# leaf_gen2_adapter.net
KiCad netlist of a schematic drawn in EAGLE
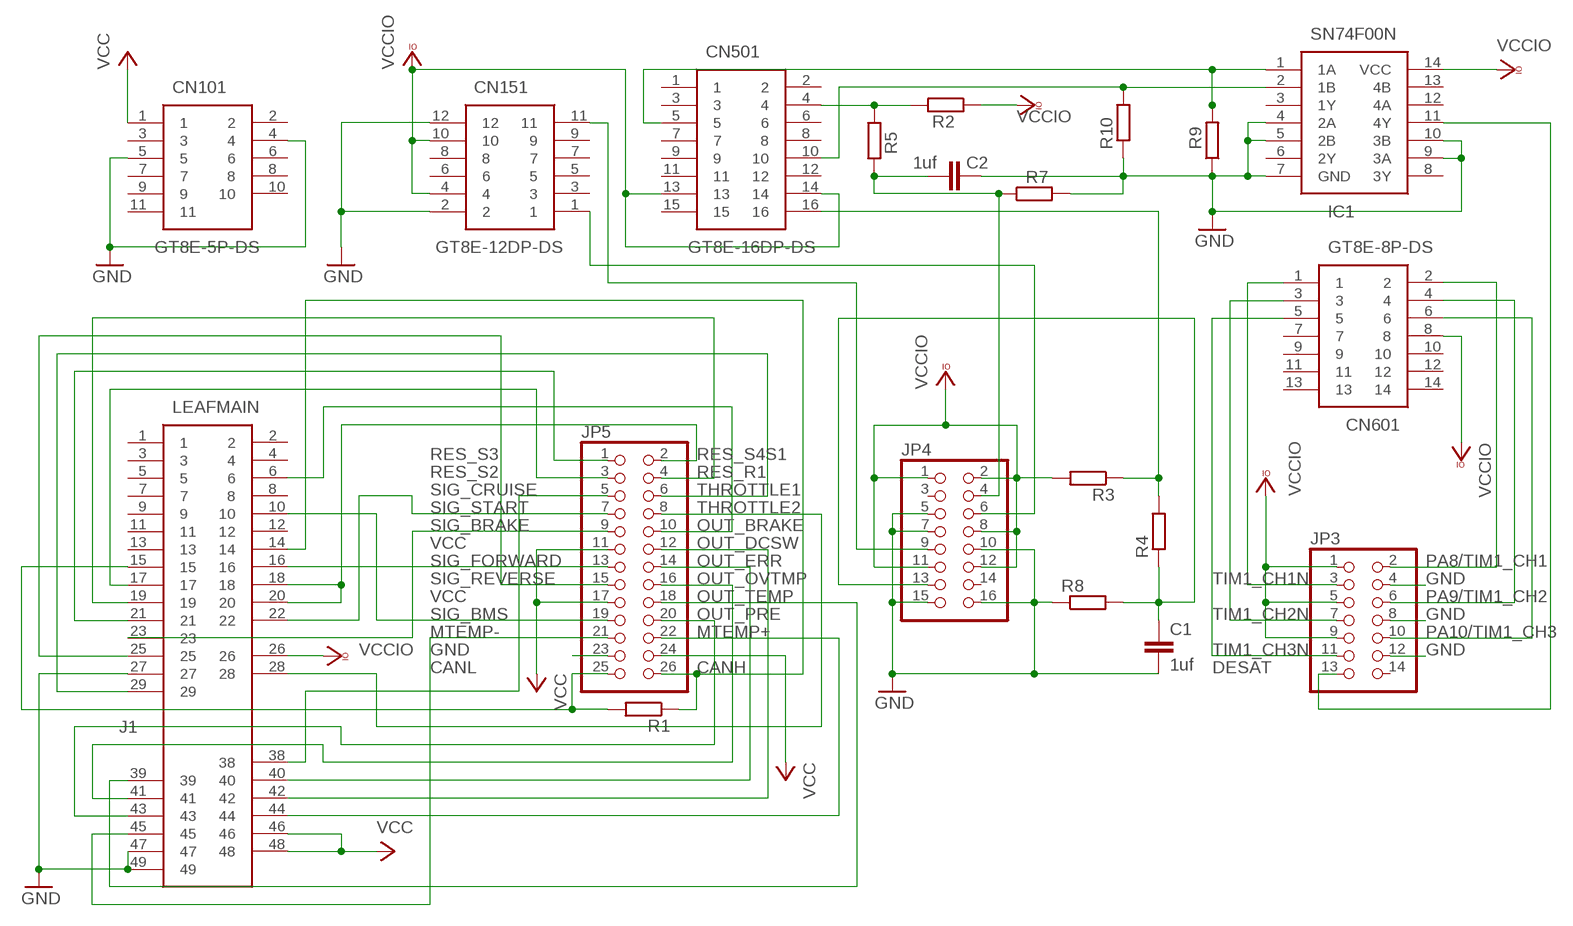
[diagram p0: schematic, sheet 1]

(export (version "E")
  (design (tool "Eeschema 10.0.6"))
  (components
    (comp (ref "C1")
      (value "1uf")
      (footprint "eagle-import:C025-024X044")
      (libsource (lib "eagle-import") (part "C-EU025-024X044"))
    )
    (comp (ref "C2")
      (value "1uf")
      (footprint "eagle-import:C025-024X044")
      (libsource (lib "eagle-import") (part "C-EU025-024X044"))
    )
    (comp (ref "CN101")
      (value "GT8E-5P-DS")
      (footprint "eagle-import:GT8E5PDS")
      (libsource (lib "eagle-import") (part "GT8E-5P-DS"))
    )
    (comp (ref "CN151")
      (value "GT8E-12DP-DS")
      (footprint "eagle-import:GT8E-12DP-DS")
      (libsource (lib "eagle-import") (part "GT8E-12DP-DS"))
    )
    (comp (ref "CN501")
      (value "GT8E-16DP-DS")
      (footprint "eagle-import:GT8E-16DP-DS")
      (libsource (lib "eagle-import") (part "GT8E-16DP-DS"))
    )
    (comp (ref "CN601")
      (value "GT8E-8P-DS")
      (footprint "eagle-import:GT8E8PDS")
      (libsource (lib "eagle-import") (part "GT8E-8P-DS"))
    )
    (comp (ref "IC1")
      (value "SN74F00N")
      (footprint "eagle-import:DIP254P762X508-14")
      (libsource (lib "eagle-import") (part "SN74F00N"))
    )
    (comp (ref "J1")
      (value "LEAFMAIN")
      (footprint "eagle-import:LEAFMAIN")
      (libsource (lib "eagle-import") (part "LEAFMAIN"))
    )
    (comp (ref "JP3")
      (value "PINHD-2X7")
      (footprint "eagle-import:2X07")
      (libsource (lib "eagle-import") (part "PINHD-2X7"))
    )
    (comp (ref "JP4")
      (value "PINHD-2X8")
      (footprint "eagle-import:2X08")
      (libsource (lib "eagle-import") (part "PINHD-2X8"))
    )
    (comp (ref "JP5")
      (value "PINHD-2X13")
      (footprint "eagle-import:2X13")
      (libsource (lib "eagle-import") (part "PINHD-2X13"))
    )
    (comp (ref "R1")
      (value "R-EU_0207/12")
      (footprint "eagle-import:0207_12")
      (libsource (lib "eagle-import") (part "R-EU_0207/12"))
    )
    (comp (ref "R2")
      (value "R-EU_0207/12")
      (footprint "eagle-import:0207_12")
      (libsource (lib "eagle-import") (part "R-EU_0207/12"))
    )
    (comp (ref "R3")
      (value "R-EU_0207/12")
      (footprint "eagle-import:0207_12")
      (libsource (lib "eagle-import") (part "R-EU_0207/12"))
    )
    (comp (ref "R4")
      (value "R-EU_0207/12")
      (footprint "eagle-import:0207_12")
      (libsource (lib "eagle-import") (part "R-EU_0207/12"))
    )
    (comp (ref "R5")
      (value "R-EU_0207/12")
      (footprint "eagle-import:0207_12")
      (libsource (lib "eagle-import") (part "R-EU_0207/12"))
    )
    (comp (ref "R7")
      (value "R-EU_0207/12")
      (footprint "eagle-import:0207_12")
      (libsource (lib "eagle-import") (part "R-EU_0207/12"))
    )
    (comp (ref "R8")
      (value "R-EU_0207/12")
      (footprint "eagle-import:0207_12")
      (libsource (lib "eagle-import") (part "R-EU_0207/12"))
    )
    (comp (ref "R9")
      (value "R-EU_0207/12")
      (footprint "eagle-import:0207_12")
      (libsource (lib "eagle-import") (part "R-EU_0207/12"))
    )
    (comp (ref "R10")
      (value "R-EU_0207/12")
      (footprint "eagle-import:0207_12")
      (libsource (lib "eagle-import") (part "R-EU_0207/12"))
    )
  )
  (nets
    (net (code "1") (name "/CANH") (class "Default")
      (node (ref "J1") (pin "14") (pinfunction "14_14") (pintype "bidirectional"))
      (node (ref "JP5") (pin "26") (pinfunction "26_26") (pintype "passive"))
      (node (ref "R1") (pin "1") (pinfunction "1_1") (pintype "passive"))
    )
    (net (code "2") (name "/CANL") (class "Default")
      (node (ref "J1") (pin "15") (pinfunction "15_15") (pintype "bidirectional"))
      (node (ref "JP5") (pin "25") (pinfunction "25_25") (pintype "passive"))
      (node (ref "R1") (pin "2") (pinfunction "2_2") (pintype "passive"))
    )
    (net (code "3") (name "/DESAT") (class "Default")
      (node (ref "IC1") (pin "11") (pinfunction "4Y_11") (pintype "bidirectional"))
      (node (ref "JP3") (pin "13") (pinfunction "13_13") (pintype "passive"))
    )
    (net (code "4") (name "/MTEMP+") (class "Default")
      (node (ref "J1") (pin "44") (pinfunction "44_44") (pintype "bidirectional"))
      (node (ref "JP5") (pin "22") (pinfunction "22_22") (pintype "passive"))
    )
    (net (code "5") (name "/MTEMP-") (class "Default")
      (node (ref "J1") (pin "45") (pinfunction "45_45") (pintype "bidirectional"))
      (node (ref "JP5") (pin "21") (pinfunction "21_21") (pintype "passive"))
    )
    (net (code "6") (name "/OUT_BRAKE") (class "Default")
      (node (ref "J1") (pin "6") (pinfunction "6_6") (pintype "bidirectional"))
      (node (ref "JP5") (pin "10") (pinfunction "10_10") (pintype "passive"))
    )
    (net (code "7") (name "/OUT_DCSW") (class "Default")
      (node (ref "J1") (pin "42") (pinfunction "42_42") (pintype "bidirectional"))
      (node (ref "JP5") (pin "12") (pinfunction "12_12") (pintype "passive"))
    )
    (net (code "8") (name "/OUT_ERR") (class "Default")
      (node (ref "J1") (pin "40") (pinfunction "40_40") (pintype "bidirectional"))
      (node (ref "JP5") (pin "14") (pinfunction "14_14") (pintype "passive"))
    )
    (net (code "9") (name "/OUT_OVTMP") (class "Default")
      (node (ref "J1") (pin "41") (pinfunction "41_41") (pintype "bidirectional"))
      (node (ref "JP5") (pin "16") (pinfunction "16_16") (pintype "passive"))
    )
    (net (code "10") (name "/OUT_PRE") (class "Default")
      (node (ref "J1") (pin "43") (pinfunction "43_43") (pintype "bidirectional"))
      (node (ref "JP5") (pin "20") (pinfunction "20_20") (pintype "passive"))
    )
    (net (code "11") (name "/OUT_TEMP") (class "Default")
      (node (ref "J1") (pin "39") (pinfunction "39_39") (pintype "bidirectional"))
      (node (ref "JP5") (pin "18") (pinfunction "18_18") (pintype "passive"))
    )
    (net (code "12") (name "/PA8{slash}TIM1_CH1") (class "Default")
      (node (ref "CN601") (pin "2") (pinfunction "2_2") (pintype "bidirectional"))
      (node (ref "JP3") (pin "2") (pinfunction "2_2") (pintype "passive"))
    )
    (net (code "13") (name "/PA9{slash}TIM1_CH2") (class "Default")
      (node (ref "CN601") (pin "4") (pinfunction "4_4") (pintype "bidirectional"))
      (node (ref "JP3") (pin "6") (pinfunction "6_6") (pintype "passive"))
    )
    (net (code "14") (name "/PA10{slash}TIM1_CH3") (class "Default")
      (node (ref "CN601") (pin "6") (pinfunction "6_6") (pintype "bidirectional"))
      (node (ref "JP3") (pin "10") (pinfunction "10_10") (pintype "passive"))
    )
    (net (code "15") (name "/RES_R1") (class "Default")
      (node (ref "J1") (pin "19") (pinfunction "19_19") (pintype "bidirectional"))
      (node (ref "JP5") (pin "4") (pinfunction "4_4") (pintype "passive"))
    )
    (net (code "16") (name "/RES_S2") (class "Default")
      (node (ref "J1") (pin "17") (pinfunction "17_17") (pintype "bidirectional"))
      (node (ref "JP5") (pin "3") (pinfunction "3_3") (pintype "passive"))
    )
    (net (code "17") (name "/RES_S3") (class "Default")
      (node (ref "J1") (pin "21") (pinfunction "21_21") (pintype "bidirectional"))
      (node (ref "JP5") (pin "1") (pinfunction "1_1") (pintype "passive"))
    )
    (net (code "18") (name "/RES_S4S1") (class "Default")
      (node (ref "J1") (pin "18") (pinfunction "18_18") (pintype "bidirectional"))
      (node (ref "J1") (pin "20") (pinfunction "20_20") (pintype "bidirectional"))
      (node (ref "JP5") (pin "2") (pinfunction "2_2") (pintype "passive"))
    )
    (net (code "19") (name "/SIG_BMS") (class "Default")
      (node (ref "J1") (pin "10") (pinfunction "10_10") (pintype "bidirectional"))
      (node (ref "JP5") (pin "19") (pinfunction "19_19") (pintype "passive"))
    )
    (net (code "20") (name "/SIG_BRAKE") (class "Default")
      (node (ref "J1") (pin "23") (pinfunction "23_23") (pintype "bidirectional"))
      (node (ref "JP5") (pin "9") (pinfunction "9_9") (pintype "passive"))
    )
    (net (code "21") (name "/SIG_CRUISE") (class "Default")
      (node (ref "J1") (pin "38") (pinfunction "38_38") (pintype "bidirectional"))
      (node (ref "JP5") (pin "5") (pinfunction "5_5") (pintype "passive"))
    )
    (net (code "22") (name "/SIG_FORWARD") (class "Default")
      (node (ref "J1") (pin "16") (pinfunction "16_16") (pintype "bidirectional"))
      (node (ref "JP5") (pin "13") (pinfunction "13_13") (pintype "passive"))
    )
    (net (code "23") (name "/SIG_REVERSE") (class "Default")
      (node (ref "J1") (pin "25") (pinfunction "25_25") (pintype "bidirectional"))
      (node (ref "JP5") (pin "15") (pinfunction "15_15") (pintype "passive"))
    )
    (net (code "24") (name "/SIG_START") (class "Default")
      (node (ref "J1") (pin "22") (pinfunction "22_22") (pintype "bidirectional"))
      (node (ref "JP5") (pin "7") (pinfunction "7_7") (pintype "passive"))
    )
    (net (code "25") (name "/THROTTLE1") (class "Default")
      (node (ref "J1") (pin "29") (pinfunction "29_29") (pintype "bidirectional"))
      (node (ref "JP5") (pin "6") (pinfunction "6_6") (pintype "passive"))
    )
    (net (code "26") (name "/THROTTLE2") (class "Default")
      (node (ref "J1") (pin "28") (pinfunction "28_28") (pintype "bidirectional"))
      (node (ref "JP5") (pin "8") (pinfunction "8_8") (pintype "passive"))
    )
    (net (code "27") (name "/TIM1_CH1N") (class "Default")
      (node (ref "CN601") (pin "1") (pinfunction "1_1") (pintype "bidirectional"))
      (node (ref "JP3") (pin "3") (pinfunction "3_3") (pintype "passive"))
    )
    (net (code "28") (name "/TIM1_CH2N") (class "Default")
      (node (ref "CN601") (pin "3") (pinfunction "3_3") (pintype "bidirectional"))
      (node (ref "JP3") (pin "7") (pinfunction "7_7") (pintype "passive"))
    )
    (net (code "29") (name "/TIM1_CH3N") (class "Default")
      (node (ref "CN601") (pin "5") (pinfunction "5_5") (pintype "bidirectional"))
      (node (ref "JP3") (pin "11") (pinfunction "11_11") (pintype "passive"))
    )
    (net (code "30") (name "GND") (class "Default")
      (node (ref "C1") (pin "2") (pinfunction "2_2") (pintype "passive"))
      (node (ref "C2") (pin "1") (pinfunction "1_1") (pintype "passive"))
      (node (ref "CN101") (pin "4") (pinfunction "4_4") (pintype "bidirectional"))
      (node (ref "CN101") (pin "5") (pinfunction "5_5") (pintype "bidirectional"))
      (node (ref "CN151") (pin "12") (pinfunction "12_12") (pintype "bidirectional"))
      (node (ref "CN151") (pin "2") (pinfunction "2_2") (pintype "bidirectional"))
      (node (ref "IC1") (pin "10") (pinfunction "3B_10") (pintype "bidirectional"))
      (node (ref "IC1") (pin "4") (pinfunction "2A_4") (pintype "bidirectional"))
      (node (ref "IC1") (pin "5") (pinfunction "2B_5") (pintype "bidirectional"))
      (node (ref "IC1") (pin "7") (pinfunction "GND_7") (pintype "bidirectional"))
      (node (ref "IC1") (pin "9") (pinfunction "3A_9") (pintype "bidirectional"))
      (node (ref "J1") (pin "27") (pinfunction "27_27") (pintype "bidirectional"))
      (node (ref "J1") (pin "47") (pinfunction "47_47") (pintype "bidirectional"))
      (node (ref "J1") (pin "49") (pinfunction "49_49") (pintype "bidirectional"))
      (node (ref "JP3") (pin "12") (pinfunction "12_12") (pintype "passive"))
      (node (ref "JP3") (pin "4") (pinfunction "4_4") (pintype "passive"))
      (node (ref "JP3") (pin "8") (pinfunction "8_8") (pintype "passive"))
      (node (ref "JP4") (pin "10") (pinfunction "10_10") (pintype "passive"))
      (node (ref "JP4") (pin "15") (pinfunction "15_15") (pintype "passive"))
      (node (ref "JP4") (pin "16") (pinfunction "16_16") (pintype "passive"))
      (node (ref "JP4") (pin "5") (pinfunction "5_5") (pintype "passive"))
      (node (ref "JP4") (pin "7") (pinfunction "7_7") (pintype "passive"))
      (node (ref "JP5") (pin "23") (pinfunction "23_23") (pintype "passive"))
      (node (ref "R10") (pin "1") (pinfunction "1_1") (pintype "passive"))
      (node (ref "R7") (pin "2") (pinfunction "2_2") (pintype "passive"))
      (node (ref "R8") (pin "1") (pinfunction "1_1") (pintype "passive"))
      (node (ref "R9") (pin "1") (pinfunction "1_1") (pintype "passive"))
    )
    (net (code "31") (name "Net-(C1-Pad1)") (class "Default")
      (node (ref "C1") (pin "1") (pinfunction "1_1") (pintype "passive"))
      (node (ref "JP4") (pin "13") (pinfunction "13_13") (pintype "passive"))
      (node (ref "R4") (pin "1") (pinfunction "1_1") (pintype "passive"))
      (node (ref "R8") (pin "2") (pinfunction "2_2") (pintype "passive"))
    )
    (net (code "32") (name "Net-(C2-Pad2)") (class "Default")
      (node (ref "C2") (pin "2") (pinfunction "2_2") (pintype "passive"))
      (node (ref "JP4") (pin "4") (pinfunction "4_4") (pintype "passive"))
      (node (ref "R5") (pin "2") (pinfunction "2_2") (pintype "passive"))
      (node (ref "R7") (pin "1") (pinfunction "1_1") (pintype "passive"))
    )
    (net (code "33") (name "Net-(CN151-Pad1)") (class "Default")
      (node (ref "CN151") (pin "1") (pinfunction "1_1") (pintype "bidirectional"))
      (node (ref "JP4") (pin "6") (pinfunction "6_6") (pintype "passive"))
    )
    (net (code "34") (name "Net-(CN151-Pad11)") (class "Default")
      (node (ref "CN151") (pin "11") (pinfunction "11_11") (pintype "bidirectional"))
      (node (ref "JP4") (pin "9") (pinfunction "9_9") (pintype "passive"))
    )
    (net (code "35") (name "Net-(CN501-Pad4)") (class "Default")
      (node (ref "CN501") (pin "4") (pinfunction "4_4") (pintype "bidirectional"))
      (node (ref "R2") (pin "2") (pinfunction "2_2") (pintype "passive"))
      (node (ref "R5") (pin "1") (pinfunction "1_1") (pintype "passive"))
    )
    (net (code "36") (name "Net-(CN501-Pad16)") (class "Default")
      (node (ref "CN501") (pin "16") (pinfunction "16_16") (pintype "bidirectional"))
      (node (ref "R3") (pin "1") (pinfunction "1_1") (pintype "passive"))
      (node (ref "R4") (pin "2") (pinfunction "2_2") (pintype "passive"))
    )
    (net (code "37") (name "Net-(IC1-1A)") (class "Default")
      (node (ref "CN501") (pin "5") (pinfunction "5_5") (pintype "bidirectional"))
      (node (ref "IC1") (pin "1") (pinfunction "1A_1") (pintype "bidirectional"))
      (node (ref "R9") (pin "2") (pinfunction "2_2") (pintype "passive"))
    )
    (net (code "38") (name "Net-(IC1-1B)") (class "Default")
      (node (ref "CN501") (pin "10") (pinfunction "10_10") (pintype "bidirectional"))
      (node (ref "IC1") (pin "2") (pinfunction "1B_2") (pintype "bidirectional"))
      (node (ref "R10") (pin "2") (pinfunction "2_2") (pintype "passive"))
    )
    (net (code "39") (name "VCC") (class "Default")
      (node (ref "CN101") (pin "1") (pinfunction "1_1") (pintype "bidirectional"))
      (node (ref "J1") (pin "46") (pinfunction "46_46") (pintype "bidirectional"))
      (node (ref "J1") (pin "48") (pinfunction "48_48") (pintype "bidirectional"))
      (node (ref "JP5") (pin "11") (pinfunction "11_11") (pintype "passive"))
      (node (ref "JP5") (pin "17") (pinfunction "17_17") (pintype "passive"))
      (node (ref "JP5") (pin "24") (pinfunction "24_24") (pintype "passive"))
    )
    (net (code "40") (name "VCCIO") (class "Default")
      (node (ref "CN151") (pin "10") (pinfunction "10_10") (pintype "bidirectional"))
      (node (ref "CN151") (pin "4") (pinfunction "4_4") (pintype "bidirectional"))
      (node (ref "CN501") (pin "13") (pinfunction "13_13") (pintype "bidirectional"))
      (node (ref "CN501") (pin "14") (pinfunction "14_14") (pintype "bidirectional"))
      (node (ref "CN601") (pin "8") (pinfunction "8_8") (pintype "bidirectional"))
      (node (ref "IC1") (pin "14") (pinfunction "VCC_14") (pintype "bidirectional"))
      (node (ref "J1") (pin "26") (pinfunction "26_26") (pintype "bidirectional"))
      (node (ref "JP3") (pin "1") (pinfunction "1_1") (pintype "passive"))
      (node (ref "JP3") (pin "5") (pinfunction "5_5") (pintype "passive"))
      (node (ref "JP3") (pin "9") (pinfunction "9_9") (pintype "passive"))
      (node (ref "JP4") (pin "1") (pinfunction "1_1") (pintype "passive"))
      (node (ref "JP4") (pin "11") (pinfunction "11_11") (pintype "passive"))
      (node (ref "JP4") (pin "12") (pinfunction "12_12") (pintype "passive"))
      (node (ref "JP4") (pin "2") (pinfunction "2_2") (pintype "passive"))
      (node (ref "JP4") (pin "8") (pinfunction "8_8") (pintype "passive"))
      (node (ref "R2") (pin "1") (pinfunction "1_1") (pintype "passive"))
      (node (ref "R3") (pin "2") (pinfunction "2_2") (pintype "passive"))
    )
    (net (code "41") (name "unconnected-(CN101-Pad2)") (class "Default")
      (node (ref "CN101") (pin "2") (pinfunction "2_2") (pintype "bidirectional"))
    )
    (net (code "42") (name "unconnected-(CN101-Pad3)") (class "Default")
      (node (ref "CN101") (pin "3") (pinfunction "3_3") (pintype "bidirectional"))
    )
    (net (code "43") (name "unconnected-(CN101-Pad6)") (class "Default")
      (node (ref "CN101") (pin "6") (pinfunction "6_6") (pintype "bidirectional"))
    )
    (net (code "44") (name "unconnected-(CN101-Pad7)") (class "Default")
      (node (ref "CN101") (pin "7") (pinfunction "7_7") (pintype "bidirectional"))
    )
    (net (code "45") (name "unconnected-(CN101-Pad8)") (class "Default")
      (node (ref "CN101") (pin "8") (pinfunction "8_8") (pintype "bidirectional"))
    )
    (net (code "46") (name "unconnected-(CN101-Pad9)") (class "Default")
      (node (ref "CN101") (pin "9") (pinfunction "9_9") (pintype "bidirectional"))
    )
    (net (code "47") (name "unconnected-(CN101-Pad10)") (class "Default")
      (node (ref "CN101") (pin "10") (pinfunction "10_10") (pintype "bidirectional"))
    )
    (net (code "48") (name "unconnected-(CN101-Pad11)") (class "Default")
      (node (ref "CN101") (pin "11") (pinfunction "11_11") (pintype "bidirectional"))
    )
    (net (code "49") (name "unconnected-(CN151-Pad3)") (class "Default")
      (node (ref "CN151") (pin "3") (pinfunction "3_3") (pintype "bidirectional"))
    )
    (net (code "50") (name "unconnected-(CN151-Pad5)") (class "Default")
      (node (ref "CN151") (pin "5") (pinfunction "5_5") (pintype "bidirectional"))
    )
    (net (code "51") (name "unconnected-(CN151-Pad6)") (class "Default")
      (node (ref "CN151") (pin "6") (pinfunction "6_6") (pintype "bidirectional"))
    )
    (net (code "52") (name "unconnected-(CN151-Pad7)") (class "Default")
      (node (ref "CN151") (pin "7") (pinfunction "7_7") (pintype "bidirectional"))
    )
    (net (code "53") (name "unconnected-(CN151-Pad8)") (class "Default")
      (node (ref "CN151") (pin "8") (pinfunction "8_8") (pintype "bidirectional"))
    )
    (net (code "54") (name "unconnected-(CN151-Pad9)") (class "Default")
      (node (ref "CN151") (pin "9") (pinfunction "9_9") (pintype "bidirectional"))
    )
    (net (code "55") (name "unconnected-(CN501-Pad1)") (class "Default")
      (node (ref "CN501") (pin "1") (pinfunction "1_1") (pintype "bidirectional"))
    )
    (net (code "56") (name "unconnected-(CN501-Pad2)") (class "Default")
      (node (ref "CN501") (pin "2") (pinfunction "2_2") (pintype "bidirectional"))
    )
    (net (code "57") (name "unconnected-(CN501-Pad3)") (class "Default")
      (node (ref "CN501") (pin "3") (pinfunction "3_3") (pintype "bidirectional"))
    )
    (net (code "58") (name "unconnected-(CN501-Pad6)") (class "Default")
      (node (ref "CN501") (pin "6") (pinfunction "6_6") (pintype "bidirectional"))
    )
    (net (code "59") (name "unconnected-(CN501-Pad7)") (class "Default")
      (node (ref "CN501") (pin "7") (pinfunction "7_7") (pintype "bidirectional"))
    )
    (net (code "60") (name "unconnected-(CN501-Pad8)") (class "Default")
      (node (ref "CN501") (pin "8") (pinfunction "8_8") (pintype "bidirectional"))
    )
    (net (code "61") (name "unconnected-(CN501-Pad9)") (class "Default")
      (node (ref "CN501") (pin "9") (pinfunction "9_9") (pintype "bidirectional"))
    )
    (net (code "62") (name "unconnected-(CN501-Pad11)") (class "Default")
      (node (ref "CN501") (pin "11") (pinfunction "11_11") (pintype "bidirectional"))
    )
    (net (code "63") (name "unconnected-(CN501-Pad12)") (class "Default")
      (node (ref "CN501") (pin "12") (pinfunction "12_12") (pintype "bidirectional"))
    )
    (net (code "64") (name "unconnected-(CN501-Pad15)") (class "Default")
      (node (ref "CN501") (pin "15") (pinfunction "15_15") (pintype "bidirectional"))
    )
    (net (code "65") (name "unconnected-(CN601-Pad7)") (class "Default")
      (node (ref "CN601") (pin "7") (pinfunction "7_7") (pintype "bidirectional"))
    )
    (net (code "66") (name "unconnected-(CN601-Pad9)") (class "Default")
      (node (ref "CN601") (pin "9") (pinfunction "9_9") (pintype "bidirectional"))
    )
    (net (code "67") (name "unconnected-(CN601-Pad10)") (class "Default")
      (node (ref "CN601") (pin "10") (pinfunction "10_10") (pintype "bidirectional"))
    )
    (net (code "68") (name "unconnected-(CN601-Pad11)") (class "Default")
      (node (ref "CN601") (pin "11") (pinfunction "11_11") (pintype "bidirectional"))
    )
    (net (code "69") (name "unconnected-(CN601-Pad12)") (class "Default")
      (node (ref "CN601") (pin "12") (pinfunction "12_12") (pintype "bidirectional"))
    )
    (net (code "70") (name "unconnected-(CN601-Pad13)") (class "Default")
      (node (ref "CN601") (pin "13") (pinfunction "13_13") (pintype "bidirectional"))
    )
    (net (code "71") (name "unconnected-(CN601-Pad14)") (class "Default")
      (node (ref "CN601") (pin "14") (pinfunction "14_14") (pintype "bidirectional"))
    )
    (net (code "72") (name "unconnected-(IC1-1Y-Pad3)") (class "Default")
      (node (ref "IC1") (pin "3") (pinfunction "1Y_3") (pintype "bidirectional"))
    )
    (net (code "73") (name "unconnected-(IC1-2Y-Pad6)") (class "Default")
      (node (ref "IC1") (pin "6") (pinfunction "2Y_6") (pintype "bidirectional"))
    )
    (net (code "74") (name "unconnected-(IC1-3Y-Pad8)") (class "Default")
      (node (ref "IC1") (pin "8") (pinfunction "3Y_8") (pintype "bidirectional"))
    )
    (net (code "75") (name "unconnected-(IC1-4A-Pad12)") (class "Default")
      (node (ref "IC1") (pin "12") (pinfunction "4A_12") (pintype "bidirectional"))
    )
    (net (code "76") (name "unconnected-(IC1-4B-Pad13)") (class "Default")
      (node (ref "IC1") (pin "13") (pinfunction "4B_13") (pintype "bidirectional"))
    )
    (net (code "77") (name "unconnected-(J1-Pad1)") (class "Default")
      (node (ref "J1") (pin "1") (pinfunction "1_1") (pintype "bidirectional"))
    )
    (net (code "78") (name "unconnected-(J1-Pad2)") (class "Default")
      (node (ref "J1") (pin "2") (pinfunction "2_2") (pintype "bidirectional"))
    )
    (net (code "79") (name "unconnected-(J1-Pad3)") (class "Default")
      (node (ref "J1") (pin "3") (pinfunction "3_3") (pintype "bidirectional"))
    )
    (net (code "80") (name "unconnected-(J1-Pad4)") (class "Default")
      (node (ref "J1") (pin "4") (pinfunction "4_4") (pintype "bidirectional"))
    )
    (net (code "81") (name "unconnected-(J1-Pad5)") (class "Default")
      (node (ref "J1") (pin "5") (pinfunction "5_5") (pintype "bidirectional"))
    )
    (net (code "82") (name "unconnected-(J1-Pad7)") (class "Default")
      (node (ref "J1") (pin "7") (pinfunction "7_7") (pintype "bidirectional"))
    )
    (net (code "83") (name "unconnected-(J1-Pad8)") (class "Default")
      (node (ref "J1") (pin "8") (pinfunction "8_8") (pintype "bidirectional"))
    )
    (net (code "84") (name "unconnected-(J1-Pad9)") (class "Default")
      (node (ref "J1") (pin "9") (pinfunction "9_9") (pintype "bidirectional"))
    )
    (net (code "85") (name "unconnected-(J1-Pad11)") (class "Default")
      (node (ref "J1") (pin "11") (pinfunction "11_11") (pintype "bidirectional"))
    )
    (net (code "86") (name "unconnected-(J1-Pad12)") (class "Default")
      (node (ref "J1") (pin "12") (pinfunction "12_12") (pintype "bidirectional"))
    )
    (net (code "87") (name "unconnected-(J1-Pad13)") (class "Default")
      (node (ref "J1") (pin "13") (pinfunction "13_13") (pintype "bidirectional"))
    )
    (net (code "88") (name "unconnected-(JP3-Pad14)") (class "Default")
      (node (ref "JP3") (pin "14") (pinfunction "14_14") (pintype "passive"))
    )
    (net (code "89") (name "unconnected-(JP4-Pad3)") (class "Default")
      (node (ref "JP4") (pin "3") (pinfunction "3_3") (pintype "passive"))
    )
    (net (code "90") (name "unconnected-(JP4-Pad14)") (class "Default")
      (node (ref "JP4") (pin "14") (pinfunction "14_14") (pintype "passive"))
    )
  )
)
